# CH32V467RET-R0.net
KiCad netlist of a schematic drawn in Altium Designer
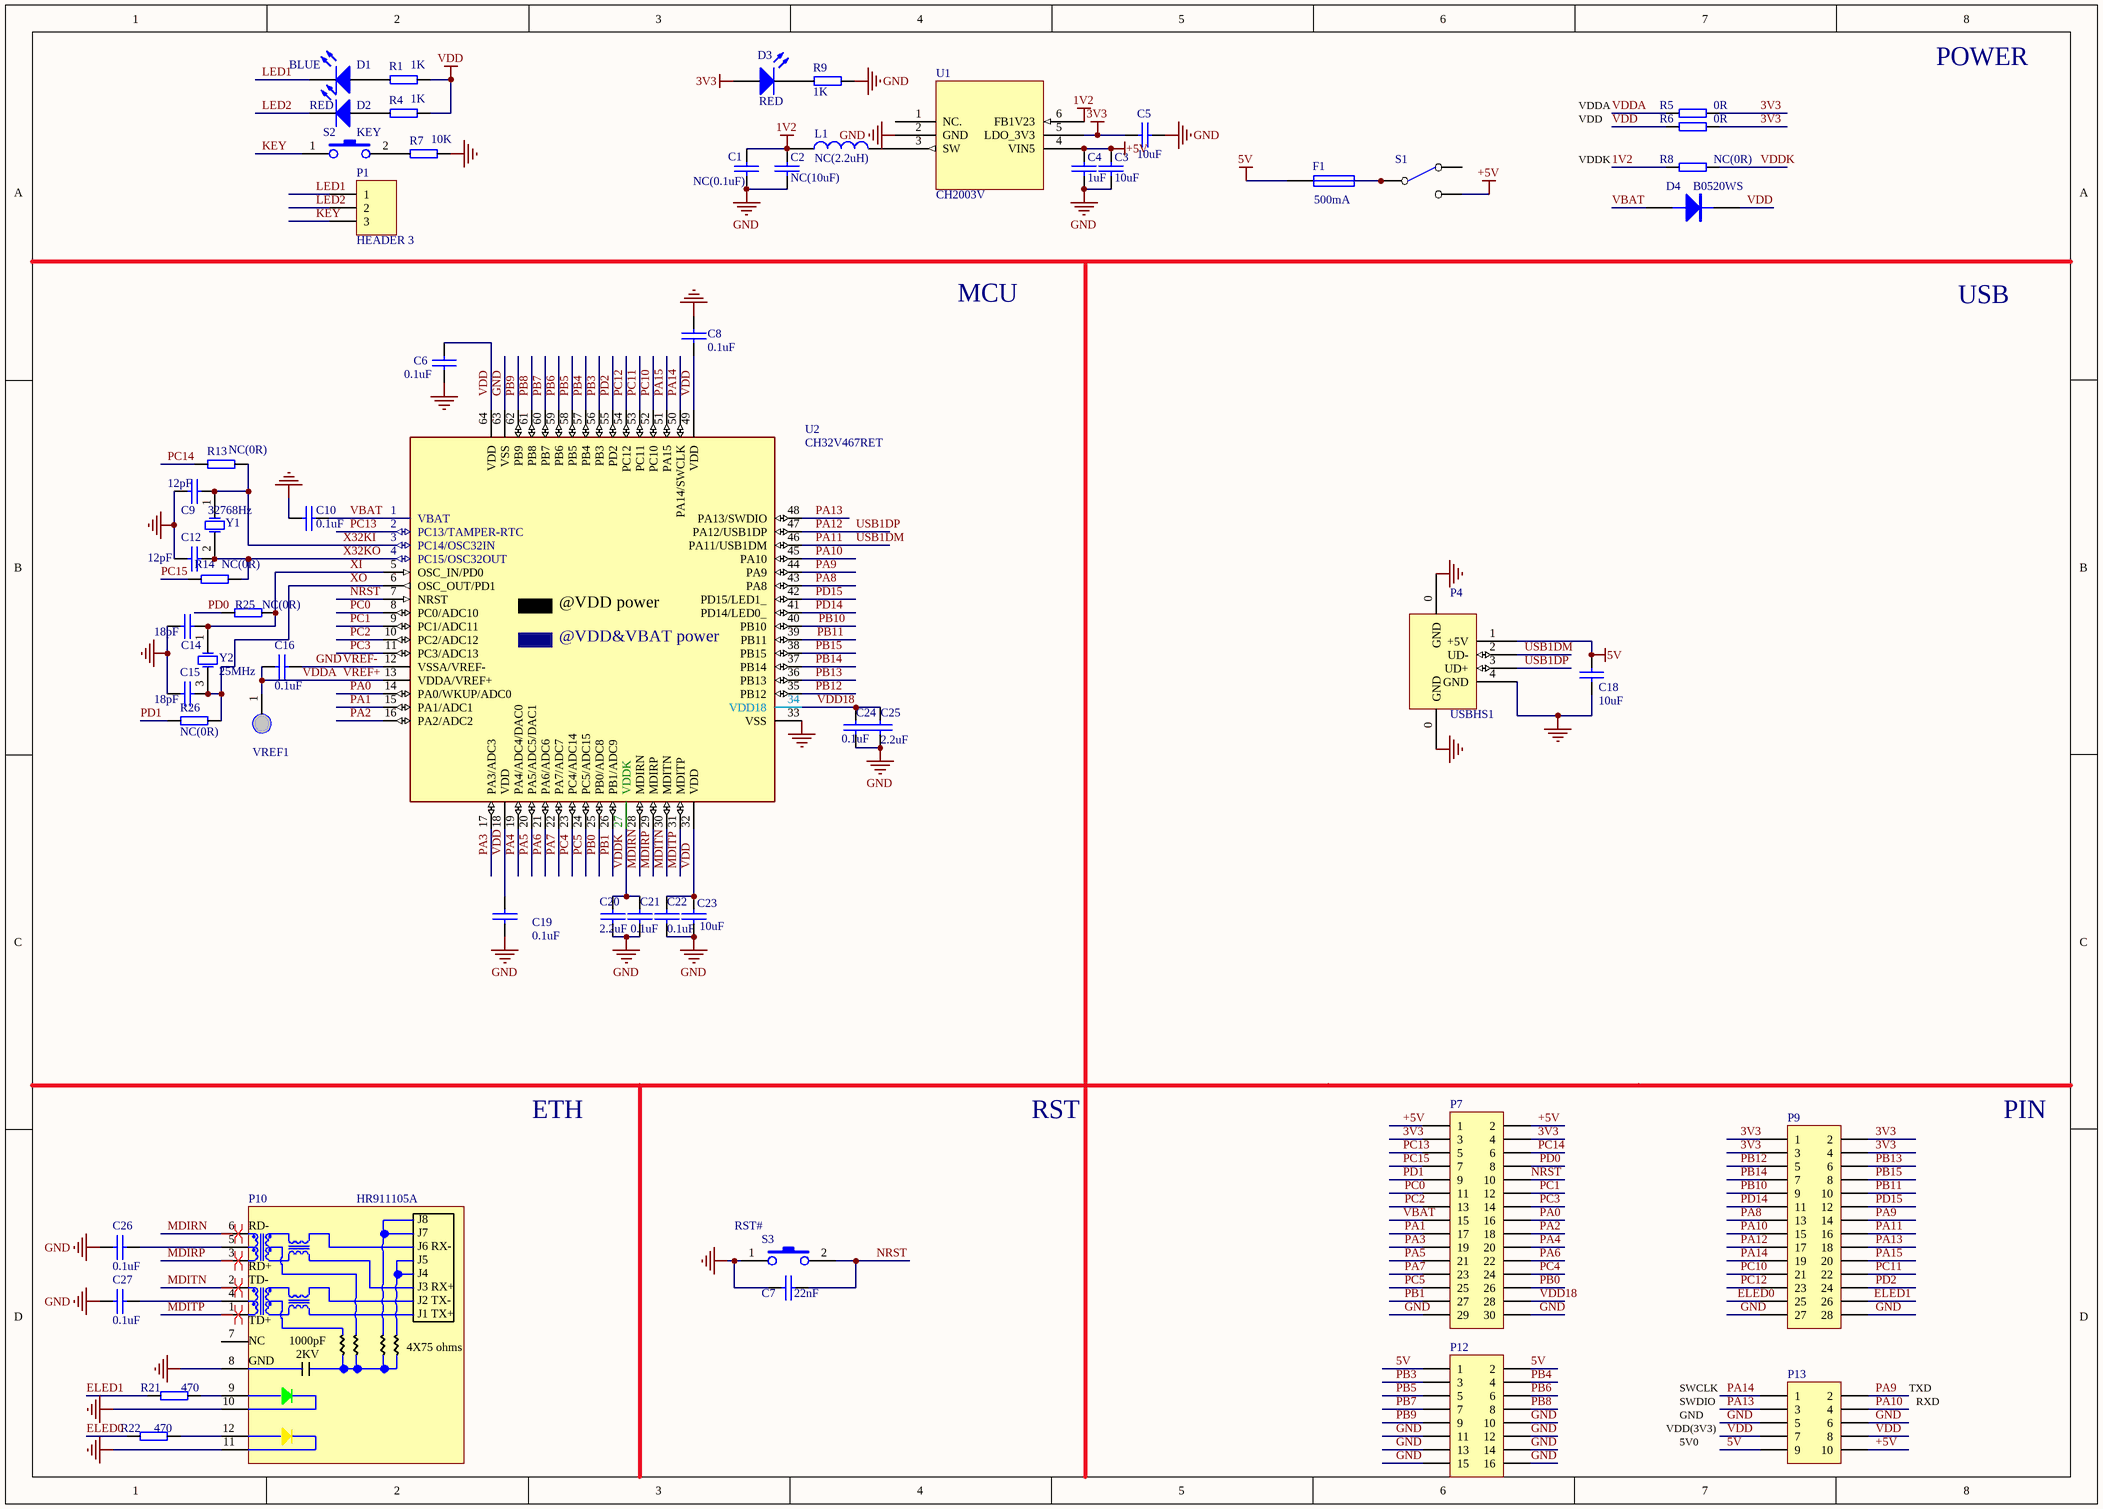
[diagram p0: CH32V467RET-R0.SchDoc]

(export (version "E")
  (design (tool "Eeschema 10.0.6"))
  (components
    (comp (ref "C1")
      (value "NC(0.1uF)")
      (footprint "0402_C")
      (description "Capacitor")
      (libsource (lib "") (part "CAP_1"))
    )
    (comp (ref "C2")
      (value "NC(10uF)")
      (footprint "0603_C")
      (description "Capacitor")
      (libsource (lib "*") (part "CAP"))
    )
    (comp (ref "C3")
      (value "10uF")
      (footprint "0603_C")
      (description "Capacitor")
      (libsource (lib "*") (part "CAP"))
    )
    (comp (ref "C4")
      (value "1uF")
      (footprint "0402_C")
      (description "Capacitor")
      (libsource (lib "") (part "CAP_1"))
    )
    (comp (ref "C5")
      (value "10uF")
      (footprint "0603_C")
      (description "Capacitor")
      (libsource (lib "*") (part "CAP"))
    )
    (comp (ref "C6")
      (value "0.1uF")
      (footprint "0402_C")
      (description "Capacitor")
      (libsource (lib "*") (part "CAP"))
    )
    (comp (ref "C7")
      (value "22nF")
      (footprint "0402_C")
      (description "Capacitor")
      (libsource (lib "") (part "CAP_2"))
    )
    (comp (ref "C8")
      (value "0.1uF")
      (footprint "0402_C")
      (description "Capacitor")
      (libsource (lib "*") (part "CAP"))
    )
    (comp (ref "C9")
      (value "12pF")
      (footprint "0402_C")
      (description "Capacitor")
      (libsource (lib "*") (part "CAP"))
    )
    (comp (ref "C10")
      (value "0.1uF")
      (footprint "0402_C")
      (description "Capacitor")
      (libsource (lib "*") (part "CAP"))
    )
    (comp (ref "C12")
      (value "12pF")
      (footprint "0402_C")
      (description "Capacitor")
      (libsource (lib "*") (part "CAP"))
    )
    (comp (ref "C14")
      (value "18pF")
      (footprint "0402_C")
      (description "Capacitor")
      (libsource (lib "*") (part "CAP"))
    )
    (comp (ref "C15")
      (value "18pF")
      (footprint "0402_C")
      (description "Capacitor")
      (libsource (lib "*") (part "CAP"))
    )
    (comp (ref "C16")
      (value "0.1uF")
      (footprint "0402_C")
      (description "Capacitor")
      (libsource (lib "*") (part "CAP"))
    )
    (comp (ref "C18")
      (value "10uF")
      (footprint "0603_C")
      (description "Capacitor")
      (libsource (lib "") (part "CAP_2"))
    )
    (comp (ref "C19")
      (value "0.1uF")
      (footprint "0402_C")
      (description "Capacitor")
      (libsource (lib "*") (part "CAP"))
    )
    (comp (ref "C20")
      (value "2.2uF")
      (footprint "0402_C")
      (description "Capacitor")
      (libsource (lib "*") (part "CAP"))
    )
    (comp (ref "C21")
      (value "0.1uF")
      (footprint "0402_C")
      (description "Capacitor")
      (libsource (lib "*") (part "CAP"))
    )
    (comp (ref "C22")
      (value "0.1uF")
      (footprint "0402_C")
      (description "Capacitor")
      (libsource (lib "*") (part "CAP"))
    )
    (comp (ref "C23")
      (value "10uF")
      (footprint "0603_C")
      (description "Capacitor")
      (libsource (lib "wch_sch_others") (part "CAP"))
    )
    (comp (ref "C24")
      (value "0.1uF")
      (footprint "0402_C")
      (description "Capacitor")
      (libsource (lib "*") (part "CAP"))
    )
    (comp (ref "C25")
      (value "2.2uF")
      (footprint "0402_C")
      (description "Capacitor")
      (libsource (lib "*") (part "CAP"))
    )
    (comp (ref "C26")
      (value "0.1uF")
      (footprint "0402_C")
      (description "Capacitor")
      (libsource (lib "wch_sch_others") (part "CAP"))
    )
    (comp (ref "C27")
      (value "0.1uF")
      (footprint "0402_C")
      (description "Capacitor")
      (libsource (lib "wch_sch_others") (part "CAP"))
    )
    (comp (ref "D1")
      (value "BLUE")
      (footprint "0603+")
      (description "Typical INFRARED GaAs LED")
      (fields (field (name "PUBLISHER") "Altium Limited"))
      (libsource (lib "*") (part "LED0"))
    )
    (comp (ref "D2")
      (value "RED")
      (footprint "0603+")
      (description "Typical INFRARED GaAs LED")
      (fields (field (name "PUBLISHER") "Altium Limited"))
      (libsource (lib "*") (part "LED0"))
    )
    (comp (ref "D3")
      (value "RED")
      (footprint "0603+")
      (description "Typical INFRARED GaAs LED")
      (fields (field (name "PUBLISHER") "Altium Limited"))
      (libsource (lib "*") (part "LED0"))
    )
    (comp (ref "D4")
      (value "B0520WS")
      (footprint "SOD-323")
      (description "Diode")
      (libsource (lib "*") (part "DIODE"))
    )
    (comp (ref "F1")
      (value "500mA")
      (footprint "0603")
      (description "Fuse")
      (libsource (lib "wch_sch_others") (part "FUSE1"))
    )
    (comp (ref "L1") (value "NC(2.2uH)") (footprint "CD32") (libsource (lib "*") (part "INDUCTOR")))
    (comp (ref "P1")
      (value "HEADER 3")
      (footprint "SIP3-2.54MM")
      (description "Header, 3-Pin")
      (libsource (lib "wch_sch_others") (part "HEADER 3"))
    )
    (comp (ref "P4")
      (value "USBHS1")
      (footprint "USBAF")
      (description "USB Port")
      (libsource (lib "*") (part "USB"))
    )
    (comp (ref "P7")
      (value "HEADER 15x2")
      (footprint "MYPCB:IDC30-2.54MM")
      (description "Header, 15-Pin, Dual row")
      (libsource (lib "wch_sch_others") (part "HEADER 15x2"))
    )
    (comp (ref "P9")
      (value "HEADER 14x2")
      (footprint "MYPCB:IDC28-2.54MM")
      (description "Header, 14-Pin, Dual row")
      (libsource (lib "wch_sch_others") (part "HEADER 14x2"))
    )
    (comp (ref "P10") (value "HR911105A") (footprint "HR911105A") (libsource (lib "*") (part "HR911105A")))
    (comp (ref "P12")
      (value "Ppin")
      (footprint "IDC16-2.54mm")
      (description "Header, 8-Pin, Dual row, Right Angle")
      (fields (field (name "PUBLISHER") "Altium Limited"))
      (libsource (lib "Miscellaneous Connectors") (part "Header 8X2H"))
    )
    (comp (ref "P13")
      (value "LINK")
      (footprint "IDC10-2.54mm")
      (description "Header, 5-Pin, Dual row, Right Angle")
      (fields (field (name "PUBLISHER") "Altium Limited"))
      (libsource (lib "Miscellaneous Connectors") (part "Header 5X2H"))
    )
    (comp (ref "R1") (value "1K") (footprint "0402") (libsource (lib "wch_sch_others") (part "RES")))
    (comp (ref "R4") (value "1K") (footprint "0402") (libsource (lib "wch_sch_others") (part "RES")))
    (comp (ref "R5") (value "0R") (footprint "0402") (libsource (lib "*") (part "R")))
    (comp (ref "R6") (value "0R") (footprint "0402") (libsource (lib "*") (part "R")))
    (comp (ref "R7") (value "10K") (footprint "0402") (libsource (lib "wch_sch_others") (part "RES")))
    (comp (ref "R8") (value "NC(0R)") (footprint "0402") (libsource (lib "*") (part "R")))
    (comp (ref "R9") (value "1K") (footprint "0402") (libsource (lib "wch_sch_others") (part "RES")))
    (comp (ref "R13") (value "NC(0R)") (footprint "0402") (libsource (lib "wch_sch_others") (part "RES")))
    (comp (ref "R14") (value "NC(0R)") (footprint "0402") (libsource (lib "wch_sch_others") (part "RES")))
    (comp (ref "R21") (value "470") (footprint "0402") (libsource (lib "wch_sch_others") (part "RES")))
    (comp (ref "R22") (value "470") (footprint "0402") (libsource (lib "wch_sch_others") (part "RES")))
    (comp (ref "R25") (value "NC(0R)") (footprint "0402") (libsource (lib "wch_sch_others") (part "RES")))
    (comp (ref "R26") (value "NC(0R)") (footprint "0402") (libsource (lib "wch_sch_others") (part "RES")))
    (comp (ref "S1") (value "SW SPDT") (footprint "SW1") (libsource (lib "*") (part "SW SPDT")))
    (comp (ref "S2")
      (value "KEY")
      (footprint "SMD_6.1x3.65x2.5mm-KEY")
      (libsource (lib "wch_sch_others") (part "KEY1"))
    )
    (comp (ref "S3")
      (value "RST#")
      (footprint "SMD_6.1x3.65x2.5mm-KEY")
      (libsource (lib "wch_sch_others") (part "KEY1"))
    )
    (comp (ref "U1")
      (value "CH2003V")
      (footprint "SOT-23-6")
      (description "Step-Down DC-DC Converter, 5V input, 1.23V * 800mA output, with LDO 3.3V * 200mA")
      (libsource (lib "CHXXX") (part "CH2003V"))
    )
    (comp (ref "U2")
      (value "CH32V467RET")
      (footprint "LQFP64_7X7")
      (description "RISC-V FPU HD-MCU, 175MHz, USB_480M, 100M Ethernet & Phy, CAN, ADC, DAC, SRAM")
      (libsource (lib "CHXXX") (part "CH32V467RET"))
    )
    (comp (ref "VREF1")
      (value "PAD")
      (footprint "TESTPOINT1")
      (description "焊盘")
      (libsource (lib "wch_sch_others") (part "PAD"))
    )
    (comp (ref "Y1")
      (value "32768Hz")
      (footprint "FC-135")
      (description "Crystal Oscillator")
      (fields (field (name "PUBLISHER") "Altium Limited"))
      (libsource (lib "*") (part "XTAL"))
    )
    (comp (ref "Y2")
      (value "25MHz")
      (footprint "XT3225")
      (description "Crystal Oscillator")
      (fields (field (name "PUBLISHER") "Altium Limited"))
      (libsource (lib "") (part "XTAL_1"))
    )
  )
  (nets
    (net (code "1") (name "+5V") (class "Default")
      (node (ref "C3") (pin "2") (pinfunction "2_2") (pintype "passive"))
      (node (ref "C4") (pin "2") (pinfunction "2_2") (pintype "passive"))
      (node (ref "P13") (pin "10") (pinfunction "10_10") (pintype "passive"))
      (node (ref "P7") (pin "1") (pinfunction "1_1") (pintype "passive"))
      (node (ref "P7") (pin "2") (pinfunction "2_2") (pintype "passive"))
      (node (ref "S1") (pin "2") (pinfunction "NC_2") (pintype "passive"))
      (node (ref "U1") (pin "4") (pinfunction "VIN5_4") (pintype "power_in"))
    )
    (net (code "3") (name "/ELED0") (class "Default")
      (node (ref "P9") (pin "25") (pinfunction "25_25") (pintype "passive"))
      (node (ref "R22") (pin "1") (pintype "passive"))
    )
    (net (code "4") (name "/ELED1") (class "Default")
      (node (ref "P9") (pin "26") (pinfunction "26_26") (pintype "passive"))
      (node (ref "R21") (pin "1") (pintype "passive"))
    )
    (net (code "5") (name "/KEY") (class "Default")
      (node (ref "P1") (pin "3") (pinfunction "3_3") (pintype "passive"))
      (node (ref "S2") (pin "1") (pinfunction "1_1") (pintype "passive"))
    )
    (net (code "6") (name "/LED1") (class "Default")
      (node (ref "D1") (pin "2") (pinfunction "K_2") (pintype "passive"))
      (node (ref "P1") (pin "1") (pinfunction "1_1") (pintype "passive"))
    )
    (net (code "7") (name "/LED2") (class "Default")
      (node (ref "D2") (pin "2") (pinfunction "K_2") (pintype "passive"))
      (node (ref "P1") (pin "2") (pinfunction "2_2") (pintype "passive"))
    )
    (net (code "8") (name "/MDIRN") (class "Default")
      (node (ref "P10") (pin "6") (pintype "passive"))
      (node (ref "U2") (pin "28") (pinfunction "MDIRN_28") (pintype "bidirectional"))
    )
    (net (code "9") (name "/MDIRP") (class "Default")
      (node (ref "P10") (pin "3") (pintype "passive"))
      (node (ref "U2") (pin "29") (pinfunction "MDIRP_29") (pintype "bidirectional"))
    )
    (net (code "10") (name "/MDITN") (class "Default")
      (node (ref "P10") (pin "2") (pintype "passive"))
      (node (ref "U2") (pin "30") (pinfunction "MDITN_30") (pintype "bidirectional"))
    )
    (net (code "11") (name "/MDITP") (class "Default")
      (node (ref "P10") (pin "1") (pintype "passive"))
      (node (ref "U2") (pin "31") (pinfunction "MDITP_31") (pintype "bidirectional"))
    )
    (net (code "12") (name "/NRST") (class "Default")
      (node (ref "C7") (pin "2") (pinfunction "2_2") (pintype "passive"))
      (node (ref "P7") (pin "10") (pinfunction "10_10") (pintype "passive"))
      (node (ref "S3") (pin "2") (pinfunction "2_2") (pintype "passive"))
      (node (ref "U2") (pin "7") (pinfunction "NRST_7") (pintype "input"))
    )
    (net (code "13") (name "/PA0") (class "Default")
      (node (ref "P7") (pin "16") (pinfunction "16_16") (pintype "passive"))
      (node (ref "U2") (pin "14") (pinfunction "PA0/WKUP/ADC0_14") (pintype "bidirectional"))
    )
    (net (code "14") (name "/PA1") (class "Default")
      (node (ref "P7") (pin "17") (pinfunction "17_17") (pintype "passive"))
      (node (ref "U2") (pin "15") (pinfunction "PA1/ADC1_15") (pintype "bidirectional"))
    )
    (net (code "15") (name "/PA2") (class "Default")
      (node (ref "P7") (pin "18") (pinfunction "18_18") (pintype "passive"))
      (node (ref "U2") (pin "16") (pinfunction "PA2/ADC2_16") (pintype "bidirectional"))
    )
    (net (code "16") (name "/PA3") (class "Default")
      (node (ref "P7") (pin "19") (pinfunction "19_19") (pintype "passive"))
      (node (ref "U2") (pin "17") (pinfunction "PA3/ADC3_17") (pintype "bidirectional"))
    )
    (net (code "17") (name "/PA4") (class "Default")
      (node (ref "P7") (pin "20") (pinfunction "20_20") (pintype "passive"))
      (node (ref "U2") (pin "19") (pinfunction "PA4/ADC4/DAC0_19") (pintype "bidirectional"))
    )
    (net (code "18") (name "/PA5") (class "Default")
      (node (ref "P7") (pin "21") (pinfunction "21_21") (pintype "passive"))
      (node (ref "U2") (pin "20") (pinfunction "PA5/ADC5/DAC1_20") (pintype "bidirectional"))
    )
    (net (code "19") (name "/PA6") (class "Default")
      (node (ref "P7") (pin "22") (pinfunction "22_22") (pintype "passive"))
      (node (ref "U2") (pin "21") (pinfunction "PA6/ADC6_21") (pintype "bidirectional"))
    )
    (net (code "20") (name "/PA7") (class "Default")
      (node (ref "P7") (pin "23") (pinfunction "23_23") (pintype "passive"))
      (node (ref "U2") (pin "22") (pinfunction "PA7/ADC7_22") (pintype "bidirectional"))
    )
    (net (code "21") (name "/PA8") (class "Default")
      (node (ref "P9") (pin "13") (pinfunction "13_13") (pintype "passive"))
      (node (ref "U2") (pin "43") (pinfunction "PA8_43") (pintype "bidirectional"))
    )
    (net (code "22") (name "/PA9") (class "Default")
      (node (ref "P13") (pin "2") (pinfunction "2_2") (pintype "passive"))
      (node (ref "P9") (pin "14") (pinfunction "14_14") (pintype "passive"))
      (node (ref "U2") (pin "44") (pinfunction "PA9_44") (pintype "bidirectional"))
    )
    (net (code "23") (name "/PA10") (class "Default")
      (node (ref "P13") (pin "4") (pinfunction "4_4") (pintype "passive"))
      (node (ref "P9") (pin "15") (pinfunction "15_15") (pintype "passive"))
      (node (ref "U2") (pin "45") (pinfunction "PA10_45") (pintype "bidirectional"))
    )
    (net (code "24") (name "/PA11") (class "Default")
      (node (ref "P4") (pin "2") (pinfunction "UD-_2") (pintype "bidirectional"))
      (node (ref "P9") (pin "16") (pinfunction "16_16") (pintype "passive"))
      (node (ref "U2") (pin "46") (pinfunction "PA11/USB1DM_46") (pintype "bidirectional"))
    )
    (net (code "25") (name "/PA12") (class "Default")
      (node (ref "P4") (pin "3") (pinfunction "UD+_3") (pintype "bidirectional"))
      (node (ref "P9") (pin "17") (pinfunction "17_17") (pintype "passive"))
      (node (ref "U2") (pin "47") (pinfunction "PA12/USB1DP_47") (pintype "bidirectional"))
    )
    (net (code "26") (name "/PA13") (class "Default")
      (node (ref "P13") (pin "3") (pinfunction "3_3") (pintype "passive"))
      (node (ref "P9") (pin "18") (pinfunction "18_18") (pintype "passive"))
      (node (ref "U2") (pin "48") (pinfunction "PA13/SWDIO_48") (pintype "bidirectional"))
    )
    (net (code "27") (name "/PA14") (class "Default")
      (node (ref "P13") (pin "1") (pinfunction "1_1") (pintype "passive"))
      (node (ref "P9") (pin "19") (pinfunction "19_19") (pintype "passive"))
      (node (ref "U2") (pin "50") (pinfunction "PA14/SWCLK_50") (pintype "bidirectional"))
    )
    (net (code "28") (name "/PA15") (class "Default")
      (node (ref "P9") (pin "20") (pinfunction "20_20") (pintype "passive"))
      (node (ref "U2") (pin "51") (pinfunction "PA15_51") (pintype "bidirectional"))
    )
    (net (code "29") (name "/PB0") (class "Default")
      (node (ref "P7") (pin "26") (pinfunction "26_26") (pintype "passive"))
      (node (ref "U2") (pin "25") (pinfunction "PB0/ADC8_25") (pintype "bidirectional"))
    )
    (net (code "30") (name "/PB1") (class "Default")
      (node (ref "P7") (pin "27") (pinfunction "27_27") (pintype "passive"))
      (node (ref "U2") (pin "26") (pinfunction "PB1/ADC9_26") (pintype "bidirectional"))
    )
    (net (code "31") (name "/PB3") (class "Default")
      (node (ref "P12") (pin "3") (pinfunction "3_3") (pintype "passive"))
      (node (ref "U2") (pin "56") (pinfunction "PB3_56") (pintype "bidirectional"))
    )
    (net (code "32") (name "/PB4") (class "Default")
      (node (ref "P12") (pin "4") (pinfunction "4_4") (pintype "passive"))
      (node (ref "U2") (pin "57") (pinfunction "PB4_57") (pintype "bidirectional"))
    )
    (net (code "33") (name "/PB5") (class "Default")
      (node (ref "P12") (pin "5") (pinfunction "5_5") (pintype "passive"))
      (node (ref "U2") (pin "58") (pinfunction "PB5_58") (pintype "bidirectional"))
    )
    (net (code "34") (name "/PB6") (class "Default")
      (node (ref "P12") (pin "6") (pinfunction "6_6") (pintype "passive"))
      (node (ref "U2") (pin "59") (pinfunction "PB6_59") (pintype "bidirectional"))
    )
    (net (code "35") (name "/PB7") (class "Default")
      (node (ref "P12") (pin "7") (pinfunction "7_7") (pintype "passive"))
      (node (ref "U2") (pin "60") (pinfunction "PB7_60") (pintype "bidirectional"))
    )
    (net (code "36") (name "/PB8") (class "Default")
      (node (ref "P12") (pin "8") (pinfunction "8_8") (pintype "passive"))
      (node (ref "U2") (pin "61") (pinfunction "PB8_61") (pintype "bidirectional"))
    )
    (net (code "37") (name "/PB9") (class "Default")
      (node (ref "P12") (pin "9") (pinfunction "9_9") (pintype "passive"))
      (node (ref "U2") (pin "62") (pinfunction "PB9_62") (pintype "bidirectional"))
    )
    (net (code "38") (name "/PB10") (class "Default")
      (node (ref "P9") (pin "9") (pinfunction "9_9") (pintype "passive"))
      (node (ref "U2") (pin "40") (pinfunction "PB10_40") (pintype "bidirectional"))
    )
    (net (code "39") (name "/PB11") (class "Default")
      (node (ref "P9") (pin "10") (pinfunction "10_10") (pintype "passive"))
      (node (ref "U2") (pin "39") (pinfunction "PB11_39") (pintype "bidirectional"))
    )
    (net (code "40") (name "/PB12") (class "Default")
      (node (ref "P9") (pin "5") (pinfunction "5_5") (pintype "passive"))
      (node (ref "U2") (pin "35") (pinfunction "PB12_35") (pintype "bidirectional"))
    )
    (net (code "41") (name "/PB13") (class "Default")
      (node (ref "P9") (pin "6") (pinfunction "6_6") (pintype "passive"))
      (node (ref "U2") (pin "36") (pinfunction "PB13_36") (pintype "bidirectional"))
    )
    (net (code "42") (name "/PB14") (class "Default")
      (node (ref "P9") (pin "7") (pinfunction "7_7") (pintype "passive"))
      (node (ref "U2") (pin "37") (pinfunction "PB14_37") (pintype "bidirectional"))
    )
    (net (code "43") (name "/PB15") (class "Default")
      (node (ref "P9") (pin "8") (pinfunction "8_8") (pintype "passive"))
      (node (ref "U2") (pin "38") (pinfunction "PB15_38") (pintype "bidirectional"))
    )
    (net (code "44") (name "/PC0") (class "Default")
      (node (ref "P7") (pin "11") (pinfunction "11_11") (pintype "passive"))
      (node (ref "U2") (pin "8") (pinfunction "PC0/ADC10_8") (pintype "bidirectional"))
    )
    (net (code "45") (name "/PC1") (class "Default")
      (node (ref "P7") (pin "12") (pinfunction "12_12") (pintype "passive"))
      (node (ref "U2") (pin "9") (pinfunction "PC1/ADC11_9") (pintype "bidirectional"))
    )
    (net (code "46") (name "/PC2") (class "Default")
      (node (ref "P7") (pin "13") (pinfunction "13_13") (pintype "passive"))
      (node (ref "U2") (pin "10") (pinfunction "PC2/ADC12_10") (pintype "bidirectional"))
    )
    (net (code "47") (name "/PC3") (class "Default")
      (node (ref "P7") (pin "14") (pinfunction "14_14") (pintype "passive"))
      (node (ref "U2") (pin "11") (pinfunction "PC3/ADC13_11") (pintype "bidirectional"))
    )
    (net (code "48") (name "/PC4") (class "Default")
      (node (ref "P7") (pin "24") (pinfunction "24_24") (pintype "passive"))
      (node (ref "U2") (pin "23") (pinfunction "PC4/ADC14_23") (pintype "bidirectional"))
    )
    (net (code "49") (name "/PC5") (class "Default")
      (node (ref "P7") (pin "25") (pinfunction "25_25") (pintype "passive"))
      (node (ref "U2") (pin "24") (pinfunction "PC5/ADC15_24") (pintype "bidirectional"))
    )
    (net (code "50") (name "/PC10") (class "Default")
      (node (ref "P9") (pin "21") (pinfunction "21_21") (pintype "passive"))
      (node (ref "U2") (pin "52") (pinfunction "PC10_52") (pintype "bidirectional"))
    )
    (net (code "51") (name "/PC11") (class "Default")
      (node (ref "P9") (pin "22") (pinfunction "22_22") (pintype "passive"))
      (node (ref "U2") (pin "53") (pinfunction "PC11_53") (pintype "bidirectional"))
    )
    (net (code "52") (name "/PC12") (class "Default")
      (node (ref "P9") (pin "23") (pinfunction "23_23") (pintype "passive"))
      (node (ref "U2") (pin "54") (pinfunction "PC12_54") (pintype "bidirectional"))
    )
    (net (code "53") (name "/PC13") (class "Default")
      (node (ref "P7") (pin "5") (pinfunction "5_5") (pintype "passive"))
      (node (ref "U2") (pin "2") (pinfunction "PC13/TAMPER-RTC_2") (pintype "bidirectional"))
    )
    (net (code "54") (name "/PC14") (class "Default")
      (node (ref "P7") (pin "6") (pinfunction "6_6") (pintype "passive"))
      (node (ref "R13") (pin "1") (pintype "passive"))
    )
    (net (code "55") (name "/PC15") (class "Default")
      (node (ref "P7") (pin "7") (pinfunction "7_7") (pintype "passive"))
      (node (ref "R14") (pin "1") (pintype "passive"))
    )
    (net (code "56") (name "/PD0") (class "Default")
      (node (ref "P7") (pin "8") (pinfunction "8_8") (pintype "passive"))
      (node (ref "R25") (pin "1") (pintype "passive"))
    )
    (net (code "57") (name "/PD1") (class "Default")
      (node (ref "P7") (pin "9") (pinfunction "9_9") (pintype "passive"))
      (node (ref "R26") (pin "2") (pintype "passive"))
    )
    (net (code "58") (name "/PD2") (class "Default")
      (node (ref "P9") (pin "24") (pinfunction "24_24") (pintype "passive"))
      (node (ref "U2") (pin "55") (pinfunction "PD2_55") (pintype "bidirectional"))
    )
    (net (code "59") (name "/PD14") (class "Default")
      (node (ref "P9") (pin "11") (pinfunction "11_11") (pintype "passive"))
      (node (ref "U2") (pin "41") (pinfunction "PD14/LED0__41") (pintype "bidirectional"))
    )
    (net (code "60") (name "/PD15") (class "Default")
      (node (ref "P9") (pin "12") (pinfunction "12_12") (pintype "passive"))
      (node (ref "U2") (pin "42") (pinfunction "PD15/LED1__42") (pintype "bidirectional"))
    )
    (net (code "61") (name "/VBAT") (class "Default")
      (node (ref "C10") (pin "2") (pinfunction "2_2") (pintype "passive"))
      (node (ref "D4") (pin "1") (pinfunction "A_1") (pintype "passive"))
      (node (ref "P7") (pin "15") (pinfunction "15_15") (pintype "passive"))
      (node (ref "U2") (pin "1") (pinfunction "VBAT_1") (pintype "power_in"))
    )
    (net (code "62") (name "/VDD18") (class "Default")
      (node (ref "C24") (pin "2") (pinfunction "2_2") (pintype "passive"))
      (node (ref "C25") (pin "2") (pinfunction "2_2") (pintype "passive"))
      (node (ref "P7") (pin "28") (pinfunction "28_28") (pintype "passive"))
      (node (ref "U2") (pin "34") (pinfunction "VDD18_34") (pintype "power_in"))
    )
    (net (code "63") (name "/VDDA") (class "Default")
      (node (ref "C16") (pin "1") (pinfunction "1_1") (pintype "passive"))
      (node (ref "R5") (pin "2") (pinfunction "2_2") (pintype "passive"))
      (node (ref "U2") (pin "13") (pinfunction "VDDA/VREF+_13") (pintype "power_in"))
      (node (ref "VREF1") (pin "1") (pintype "passive"))
    )
    (net (code "64") (name "/VDDK") (class "Default")
      (node (ref "C20") (pin "2") (pinfunction "2_2") (pintype "passive"))
      (node (ref "C21") (pin "2") (pinfunction "2_2") (pintype "passive"))
      (node (ref "R8") (pin "1") (pinfunction "1_1") (pintype "passive"))
      (node (ref "U2") (pin "27") (pinfunction "VDDK_27") (pintype "power_in"))
    )
    (net (code "65") (name "/X32KI") (class "Default")
      (node (ref "C9") (pin "2") (pinfunction "2_2") (pintype "passive"))
      (node (ref "R13") (pin "2") (pintype "passive"))
      (node (ref "U2") (pin "3") (pinfunction "PC14/OSC32IN_3") (pintype "bidirectional"))
      (node (ref "Y1") (pin "1") (pinfunction "OSC1_1") (pintype "passive"))
    )
    (net (code "66") (name "/X32KO") (class "Default")
      (node (ref "C12") (pin "2") (pinfunction "2_2") (pintype "passive"))
      (node (ref "R14") (pin "2") (pintype "passive"))
      (node (ref "U2") (pin "4") (pinfunction "PC15/OSC32OUT_4") (pintype "bidirectional"))
      (node (ref "Y1") (pin "2") (pinfunction "OSC2_2") (pintype "passive"))
    )
    (net (code "67") (name "/XI") (class "Default")
      (node (ref "C14") (pin "2") (pinfunction "2_2") (pintype "passive"))
      (node (ref "R25") (pin "2") (pintype "passive"))
      (node (ref "U2") (pin "5") (pinfunction "OSC_IN/PD0_5") (pintype "input"))
      (node (ref "Y2") (pin "1") (pinfunction "OSC1_1") (pintype "passive"))
    )
    (net (code "68") (name "/XO") (class "Default")
      (node (ref "C15") (pin "2") (pinfunction "2_2") (pintype "passive"))
      (node (ref "R26") (pin "1") (pintype "passive"))
      (node (ref "U2") (pin "6") (pinfunction "OSC_OUT/PD1_6") (pintype "output"))
      (node (ref "Y2") (pin "3") (pinfunction "OSC2_3") (pintype "passive"))
    )
    (net (code "69") (name "1V2") (class "Default")
      (node (ref "C1") (pin "2") (pinfunction "2_2") (pintype "passive"))
      (node (ref "C2") (pin "2") (pinfunction "2_2") (pintype "passive"))
      (node (ref "L1") (pin "2") (pinfunction "2_2") (pintype "passive"))
      (node (ref "R8") (pin "2") (pinfunction "2_2") (pintype "passive"))
      (node (ref "U1") (pin "6") (pinfunction "FB1V23_6") (pintype "input"))
    )
    (net (code "70") (name "3V3") (class "Default")
      (node (ref "C5") (pin "2") (pinfunction "2_2") (pintype "passive"))
      (node (ref "D3") (pin "1") (pinfunction "A_1") (pintype "passive"))
      (node (ref "P7") (pin "3") (pinfunction "3_3") (pintype "passive"))
      (node (ref "P7") (pin "4") (pinfunction "4_4") (pintype "passive"))
      (node (ref "P9") (pin "1") (pinfunction "1_1") (pintype "passive"))
      (node (ref "P9") (pin "2") (pinfunction "2_2") (pintype "passive"))
      (node (ref "P9") (pin "3") (pinfunction "3_3") (pintype "passive"))
      (node (ref "P9") (pin "4") (pinfunction "4_4") (pintype "passive"))
      (node (ref "R5") (pin "1") (pinfunction "1_1") (pintype "passive"))
      (node (ref "R6") (pin "1") (pinfunction "1_1") (pintype "passive"))
      (node (ref "U1") (pin "5") (pinfunction "LDO_3V3_5") (pintype "power_in"))
    )
    (net (code "71") (name "5V") (class "Default")
      (node (ref "C18") (pin "1") (pinfunction "1_1") (pintype "passive"))
      (node (ref "F1") (pin "1") (pinfunction "1_1") (pintype "passive"))
      (node (ref "P12") (pin "1") (pinfunction "1_1") (pintype "passive"))
      (node (ref "P12") (pin "2") (pinfunction "2_2") (pintype "passive"))
      (node (ref "P13") (pin "9") (pinfunction "9_9") (pintype "passive"))
      (node (ref "P4") (pin "1") (pinfunction "+5V_1") (pintype "power_in"))
    )
    (net (code "72") (name "GND") (class "Default")
      (node (ref "C1") (pin "1") (pinfunction "1_1") (pintype "passive"))
      (node (ref "C10") (pin "1") (pinfunction "1_1") (pintype "passive"))
      (node (ref "C12") (pin "1") (pinfunction "1_1") (pintype "passive"))
      (node (ref "C14") (pin "1") (pinfunction "1_1") (pintype "passive"))
      (node (ref "C15") (pin "1") (pinfunction "1_1") (pintype "passive"))
      (node (ref "C16") (pin "2") (pinfunction "2_2") (pintype "passive"))
      (node (ref "C18") (pin "2") (pinfunction "2_2") (pintype "passive"))
      (node (ref "C19") (pin "1") (pinfunction "1_1") (pintype "passive"))
      (node (ref "C2") (pin "1") (pinfunction "1_1") (pintype "passive"))
      (node (ref "C20") (pin "1") (pinfunction "1_1") (pintype "passive"))
      (node (ref "C21") (pin "1") (pinfunction "1_1") (pintype "passive"))
      (node (ref "C22") (pin "1") (pinfunction "1_1") (pintype "passive"))
      (node (ref "C23") (pin "1") (pinfunction "1_1") (pintype "passive"))
      (node (ref "C24") (pin "1") (pinfunction "1_1") (pintype "passive"))
      (node (ref "C25") (pin "1") (pinfunction "1_1") (pintype "passive"))
      (node (ref "C26") (pin "1") (pinfunction "1_1") (pintype "passive"))
      (node (ref "C27") (pin "1") (pinfunction "1_1") (pintype "passive"))
      (node (ref "C3") (pin "1") (pinfunction "1_1") (pintype "passive"))
      (node (ref "C4") (pin "1") (pinfunction "1_1") (pintype "passive"))
      (node (ref "C5") (pin "1") (pinfunction "1_1") (pintype "passive"))
      (node (ref "C6") (pin "1") (pinfunction "1_1") (pintype "passive"))
      (node (ref "C7") (pin "1") (pinfunction "1_1") (pintype "passive"))
      (node (ref "C8") (pin "2") (pinfunction "2_2") (pintype "passive"))
      (node (ref "C9") (pin "1") (pinfunction "1_1") (pintype "passive"))
      (node (ref "P10") (pin "10") (pintype "passive"))
      (node (ref "P10") (pin "11") (pintype "passive"))
      (node (ref "P10") (pin "8") (pintype "passive"))
      (node (ref "P12") (pin "10") (pinfunction "10_10") (pintype "passive"))
      (node (ref "P12") (pin "11") (pinfunction "11_11") (pintype "passive"))
      (node (ref "P12") (pin "12") (pinfunction "12_12") (pintype "passive"))
      (node (ref "P12") (pin "13") (pinfunction "13_13") (pintype "passive"))
      (node (ref "P12") (pin "14") (pinfunction "14_14") (pintype "passive"))
      (node (ref "P12") (pin "15") (pinfunction "15_15") (pintype "passive"))
      (node (ref "P12") (pin "16") (pinfunction "16_16") (pintype "passive"))
      (node (ref "P13") (pin "5") (pinfunction "5_5") (pintype "passive"))
      (node (ref "P13") (pin "6") (pinfunction "6_6") (pintype "passive"))
      (node (ref "P4") (pin "0") (pinfunction "GND_0") (pintype "power_in"))
      (node (ref "P4") (pin "4") (pinfunction "GND_4") (pintype "power_in"))
      (node (ref "P7") (pin "29") (pinfunction "29_29") (pintype "passive"))
      (node (ref "P7") (pin "30") (pinfunction "30_30") (pintype "passive"))
      (node (ref "P9") (pin "27") (pinfunction "27_27") (pintype "passive"))
      (node (ref "P9") (pin "28") (pinfunction "28_28") (pintype "passive"))
      (node (ref "R7") (pin "1") (pintype "passive"))
      (node (ref "R9") (pin "2") (pintype "passive"))
      (node (ref "S3") (pin "1") (pinfunction "1_1") (pintype "passive"))
      (node (ref "U1") (pin "2") (pinfunction "GND_2") (pintype "power_in"))
      (node (ref "U2") (pin "12") (pinfunction "VSSA/VREF-_12") (pintype "power_in"))
      (node (ref "U2") (pin "33") (pinfunction "VSS_33") (pintype "power_in"))
      (node (ref "U2") (pin "63") (pinfunction "VSS_63") (pintype "power_in"))
    )
    (net (code "73") (name "Net-(C26-Pad2)") (class "Default")
      (node (ref "C26") (pin "2") (pinfunction "2_2") (pintype "passive"))
      (node (ref "P10") (pin "5") (pintype "passive"))
    )
    (net (code "74") (name "Net-(C27-Pad2)") (class "Default")
      (node (ref "C27") (pin "2") (pinfunction "2_2") (pintype "passive"))
      (node (ref "P10") (pin "4") (pintype "passive"))
    )
    (net (code "75") (name "Net-(D1-A)") (class "Default")
      (node (ref "D1") (pin "1") (pinfunction "A_1") (pintype "passive"))
      (node (ref "R1") (pin "2") (pintype "passive"))
    )
    (net (code "76") (name "Net-(D2-A)") (class "Default")
      (node (ref "D2") (pin "1") (pinfunction "A_1") (pintype "passive"))
      (node (ref "R4") (pin "2") (pintype "passive"))
    )
    (net (code "77") (name "Net-(D3-K)") (class "Default")
      (node (ref "D3") (pin "2") (pinfunction "K_2") (pintype "passive"))
      (node (ref "R9") (pin "1") (pintype "passive"))
    )
    (net (code "78") (name "Net-(P10-Pad9)") (class "Default")
      (node (ref "P10") (pin "9") (pintype "passive"))
      (node (ref "R21") (pin "2") (pintype "passive"))
    )
    (net (code "79") (name "Net-(P10-Pad12)") (class "Default")
      (node (ref "P10") (pin "12") (pintype "passive"))
      (node (ref "R22") (pin "2") (pintype "passive"))
    )
    (net (code "80") (name "Net-(R7-Pad2)") (class "Default")
      (node (ref "R7") (pin "2") (pintype "passive"))
      (node (ref "S2") (pin "2") (pinfunction "2_2") (pintype "passive"))
    )
    (net (code "81") (name "Net-(S1-COMMON)") (class "Default")
      (node (ref "F1") (pin "2") (pinfunction "2_2") (pintype "passive"))
      (node (ref "S1") (pin "1") (pinfunction "COMMON_1") (pintype "passive"))
    )
    (net (code "82") (name "Net-(U1-SW)") (class "Default")
      (node (ref "L1") (pin "1") (pinfunction "1_1") (pintype "passive"))
      (node (ref "U1") (pin "3") (pinfunction "SW_3") (pintype "output"))
    )
    (net (code "83") (name "VDD") (class "Default")
      (node (ref "C19") (pin "2") (pinfunction "2_2") (pintype "passive"))
      (node (ref "C22") (pin "2") (pinfunction "2_2") (pintype "passive"))
      (node (ref "C23") (pin "2") (pinfunction "2_2") (pintype "passive"))
      (node (ref "C6") (pin "2") (pinfunction "2_2") (pintype "passive"))
      (node (ref "C8") (pin "1") (pinfunction "1_1") (pintype "passive"))
      (node (ref "D4") (pin "2") (pinfunction "K_2") (pintype "passive"))
      (node (ref "P13") (pin "7") (pinfunction "7_7") (pintype "passive"))
      (node (ref "P13") (pin "8") (pinfunction "8_8") (pintype "passive"))
      (node (ref "R1") (pin "1") (pintype "passive"))
      (node (ref "R4") (pin "1") (pintype "passive"))
      (node (ref "R6") (pin "2") (pinfunction "2_2") (pintype "passive"))
      (node (ref "U2") (pin "18") (pinfunction "VDD_18") (pintype "power_in"))
      (node (ref "U2") (pin "32") (pinfunction "VDD_32") (pintype "power_in"))
      (node (ref "U2") (pin "49") (pinfunction "VDD_49") (pintype "power_in"))
      (node (ref "U2") (pin "64") (pinfunction "VDD_64") (pintype "power_in"))
    )
    (net (code "84") (name "unconnected-(P10-Pad7)") (class "Default")
      (node (ref "P10") (pin "7") (pintype "passive"))
    )
    (net (code "85") (name "unconnected-(S1-NO-Pad3)") (class "Default")
      (node (ref "S1") (pin "3") (pinfunction "NO_3") (pintype "passive"))
    )
    (net (code "86") (name "unconnected-(U1-NC.-Pad1)") (class "Default")
      (node (ref "U1") (pin "1") (pinfunction "NC._1") (pintype "passive"))
    )
  )
)
